# 220_cup_wash_sucction.net
KiCad netlist of a schematic drawn in EAGLE
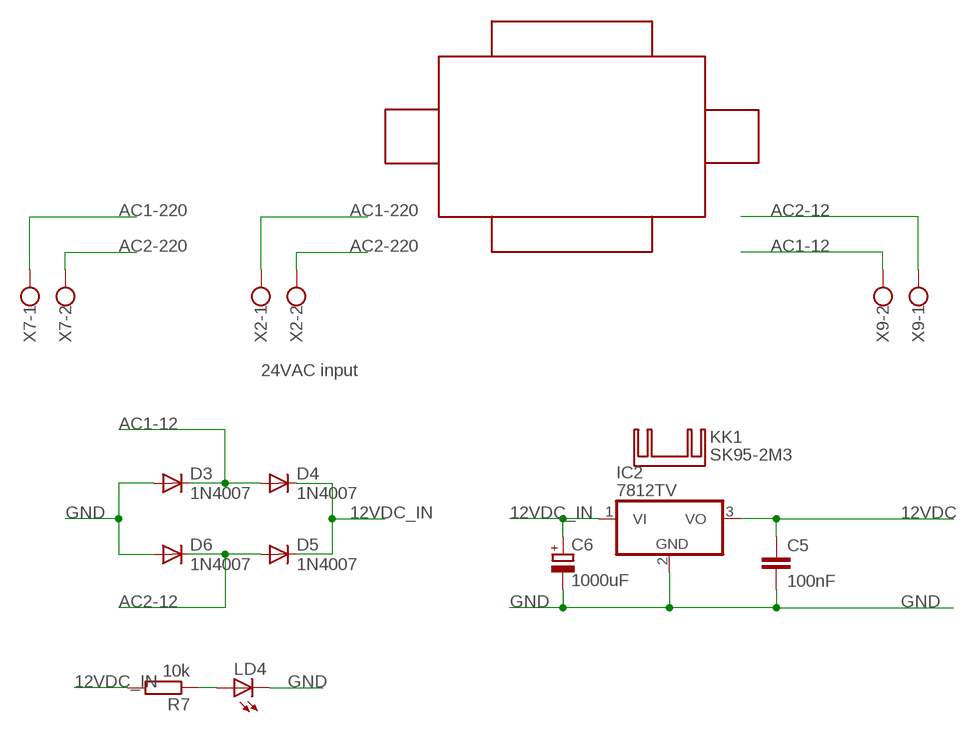
[diagram p0: schematic, sheet 1]
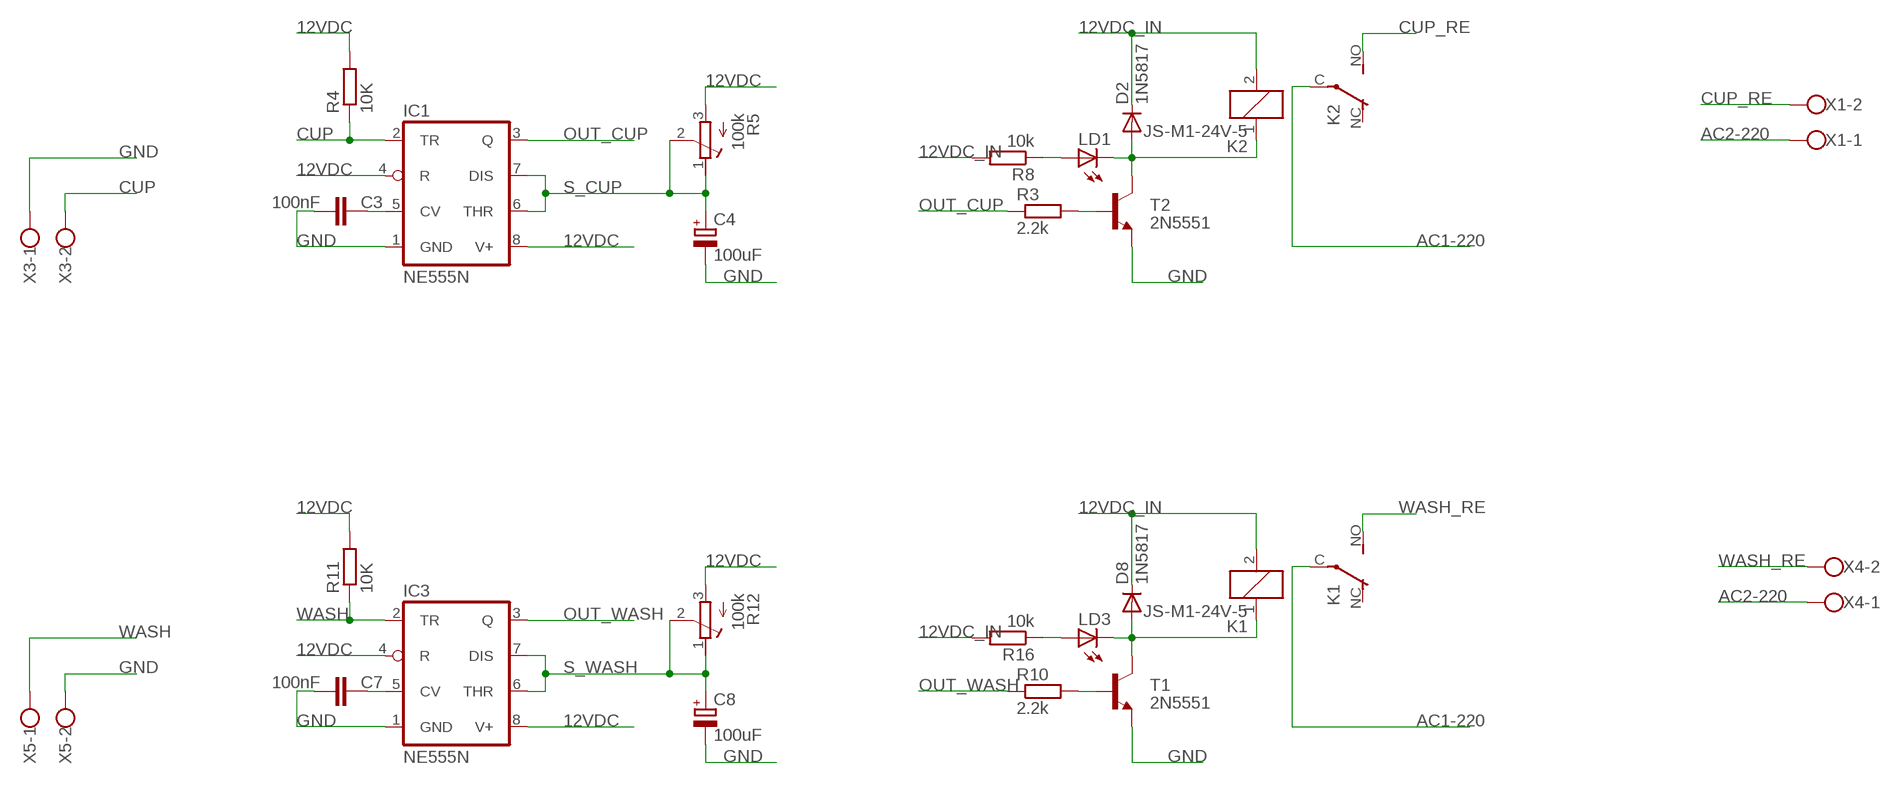
[diagram p1: schematic, sheet 2]
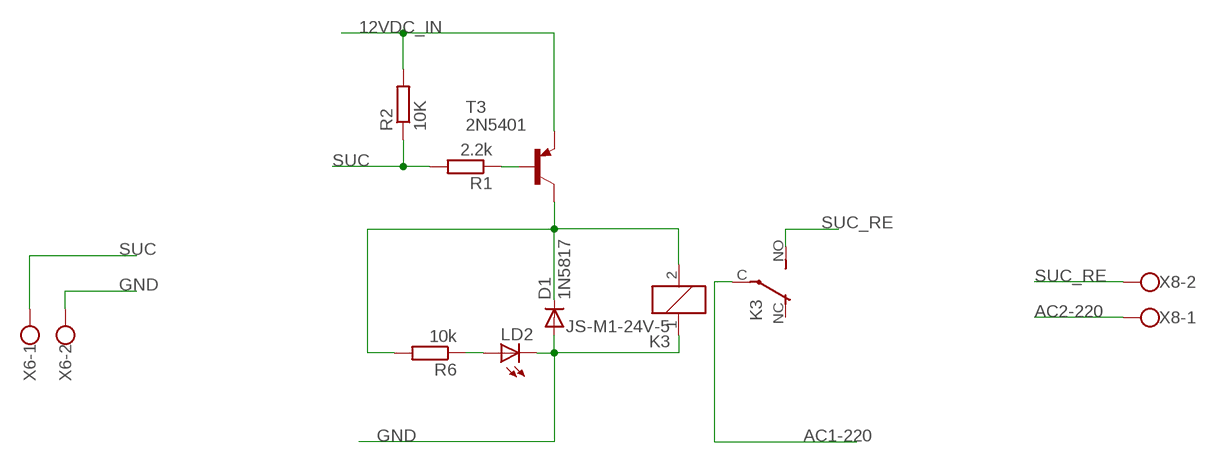
[diagram p2: schematic, sheet 3]

(export (version "E")
  (design (tool "Eeschema 10.0.6"))
  (components
    (comp (ref "D1")
      (value "1N5817")
      (footprint "eagle-import:DO41-10")
      (libsource (lib "eagle-import") (part "1N4004"))
    )
    (comp (ref "K3")
      (value "JS-M1-24V-5")
      (footprint "eagle-import:JS-M")
      (fields (field (name "MF") "FARNELL") (field (name "MPN") "JSM1-12V-5"))
      (libsource (lib "eagle-import") (part "JS-M1-12V-5"))
    )
    (comp (ref "LD2")
      (value "LED5MM")
      (footprint "eagle-import:LED5MM")
      (libsource (lib "eagle-import") (part "LED5MM"))
    )
    (comp (ref "R1")
      (value "2.2k")
      (footprint "eagle-import:0207_10")
      (libsource (lib "eagle-import") (part "R-EU_0207/10"))
    )
    (comp (ref "R2")
      (value "10K")
      (footprint "eagle-import:0207_10")
      (libsource (lib "eagle-import") (part "R-EU_0207/10"))
    )
    (comp (ref "R6")
      (value "10k")
      (footprint "eagle-import:0207_10")
      (libsource (lib "eagle-import") (part "R-EU_0207/10"))
    )
    (comp (ref "T3")
      (value "2N5401")
      (footprint "eagle-import:TO92-EBC")
      (libsource (lib "eagle-import") (part "-PNP-TO92-EBC2N5401"))
    )
    (comp (ref "X6")
      (value "W237-102")
      (footprint "eagle-import:W237-102")
      (libsource (lib "eagle-import") (part "W237-102"))
    )
    (comp (ref "X8")
      (value "W237-102")
      (footprint "eagle-import:W237-102")
      (libsource (lib "eagle-import") (part "W237-102"))
    )
    (comp (ref "C3")
      (value "100nF")
      (footprint "eagle-import:C050-025X075")
      (libsource (lib "eagle-import") (part "C-EU050-025X075"))
    )
    (comp (ref "C4")
      (value "100uF")
      (footprint "eagle-import:E3,5-8")
      (libsource (lib "eagle-import") (part "CPOL-EUE3.5-8"))
    )
    (comp (ref "C7")
      (value "100nF")
      (footprint "eagle-import:C050-025X075")
      (libsource (lib "eagle-import") (part "C-EU050-025X075"))
    )
    (comp (ref "C8")
      (value "100uF")
      (footprint "eagle-import:E3,5-8")
      (libsource (lib "eagle-import") (part "CPOL-EUE3.5-8"))
    )
    (comp (ref "D2")
      (value "1N5817")
      (footprint "eagle-import:DO41-10")
      (libsource (lib "eagle-import") (part "1N4004"))
    )
    (comp (ref "D8")
      (value "1N5817")
      (footprint "eagle-import:DO41-10")
      (libsource (lib "eagle-import") (part "1N4004"))
    )
    (comp (ref "IC1")
      (value "NE555N")
      (footprint "eagle-import:DIL08-ROUND")
      (libsource (lib "eagle-import") (part "555NNE"))
    )
    (comp (ref "IC3")
      (value "NE555N")
      (footprint "eagle-import:DIL08-ROUND")
      (libsource (lib "eagle-import") (part "555NNE"))
    )
    (comp (ref "K1")
      (value "JS-M1-24V-5")
      (footprint "eagle-import:JS-M")
      (fields (field (name "MF") "FARNELL") (field (name "MPN") "JSM1-12V-5"))
      (libsource (lib "eagle-import") (part "JS-M1-12V-5"))
    )
    (comp (ref "K2")
      (value "JS-M1-24V-5")
      (footprint "eagle-import:JS-M")
      (fields (field (name "MF") "FARNELL") (field (name "MPN") "JSM1-12V-5"))
      (libsource (lib "eagle-import") (part "JS-M1-12V-5"))
    )
    (comp (ref "LD1")
      (value "LED5MM")
      (footprint "eagle-import:LED5MM")
      (libsource (lib "eagle-import") (part "LED5MM"))
    )
    (comp (ref "LD3")
      (value "LED5MM")
      (footprint "eagle-import:LED5MM")
      (libsource (lib "eagle-import") (part "LED5MM"))
    )
    (comp (ref "R3")
      (value "2.2k")
      (footprint "eagle-import:0207_10")
      (libsource (lib "eagle-import") (part "R-EU_0207/10"))
    )
    (comp (ref "R4")
      (value "10K")
      (footprint "eagle-import:0207_10")
      (libsource (lib "eagle-import") (part "R-EU_0207/10"))
    )
    (comp (ref "R5")
      (value "100k")
      (footprint "eagle-import:RTRIMT93XA")
      (libsource (lib "eagle-import") (part "R-TRIMMT93XA"))
    )
    (comp (ref "R8")
      (value "10k")
      (footprint "eagle-import:0207_10")
      (libsource (lib "eagle-import") (part "R-EU_0207/10"))
    )
    (comp (ref "R10")
      (value "2.2k")
      (footprint "eagle-import:0207_10")
      (libsource (lib "eagle-import") (part "R-EU_0207/10"))
    )
    (comp (ref "R11")
      (value "10K")
      (footprint "eagle-import:0207_10")
      (libsource (lib "eagle-import") (part "R-EU_0207/10"))
    )
    (comp (ref "R12")
      (value "100k")
      (footprint "eagle-import:RTRIMT93XA")
      (libsource (lib "eagle-import") (part "R-TRIMMT93XA"))
    )
    (comp (ref "R16")
      (value "10k")
      (footprint "eagle-import:0207_10")
      (libsource (lib "eagle-import") (part "R-EU_0207/10"))
    )
    (comp (ref "T1")
      (value "2N5551")
      (footprint "eagle-import:TO92-EBC-OVAL")
      (libsource (lib "eagle-import") (part "2N2222"))
    )
    (comp (ref "T2")
      (value "2N5551")
      (footprint "eagle-import:TO92-EBC-OVAL")
      (libsource (lib "eagle-import") (part "2N2222"))
    )
    (comp (ref "X1")
      (value "W237-102")
      (footprint "eagle-import:W237-102")
      (libsource (lib "eagle-import") (part "W237-102"))
    )
    (comp (ref "X3")
      (value "W237-102")
      (footprint "eagle-import:W237-102")
      (libsource (lib "eagle-import") (part "W237-102"))
    )
    (comp (ref "X4")
      (value "W237-102")
      (footprint "eagle-import:W237-102")
      (libsource (lib "eagle-import") (part "W237-102"))
    )
    (comp (ref "X5")
      (value "W237-102")
      (footprint "eagle-import:W237-102")
      (libsource (lib "eagle-import") (part "W237-102"))
    )
    (comp (ref "C5")
      (value "100nF")
      (footprint "eagle-import:C050-025X075")
      (libsource (lib "eagle-import") (part "C-EU050-025X075"))
    )
    (comp (ref "C6")
      (value "1000uF")
      (footprint "eagle-import:E3,5-10")
      (libsource (lib "eagle-import") (part "CPOL-EUE3.5-10"))
    )
    (comp (ref "D3")
      (value "1N4007")
      (footprint "eagle-import:DO41-10")
      (libsource (lib "eagle-import") (part "adafruit_420_1N4004"))
    )
    (comp (ref "D4")
      (value "1N4007")
      (footprint "eagle-import:DO41-10")
      (libsource (lib "eagle-import") (part "adafruit_420_1N4004"))
    )
    (comp (ref "D5")
      (value "1N4007")
      (footprint "eagle-import:DO41-10")
      (libsource (lib "eagle-import") (part "adafruit_420_1N4004"))
    )
    (comp (ref "D6")
      (value "1N4007")
      (footprint "eagle-import:DO41-10")
      (libsource (lib "eagle-import") (part "adafruit_420_1N4004"))
    )
    (comp (ref "IC2")
      (value "7812TV")
      (footprint "eagle-import:TO220V")
      (libsource (lib "eagle-import") (part "78TV12"))
    )
    (comp (ref "KK1")
      (value "SK95-2M3")
      (footprint "eagle-import:SK95-2M3")
      (libsource (lib "eagle-import") (part "SK95-2M3"))
    )
    (comp (ref "LD4")
      (value "LED5MM")
      (footprint "eagle-import:LED5MM")
      (libsource (lib "eagle-import") (part "LED5MM"))
    )
    (comp (ref "R7")
      (value "10k")
      (footprint "eagle-import:0207_10")
      (libsource (lib "eagle-import") (part "R-EU_0207/10"))
    )
    (comp (ref "U$1")
      (value "TRANS_12V")
      (footprint "eagle-import:12V")
      (libsource (lib "eagle-import") (part "TRANS_12V"))
    )
    (comp (ref "X2")
      (value "W237-102")
      (footprint "eagle-import:W237-102")
      (libsource (lib "eagle-import") (part "W237-102"))
    )
    (comp (ref "X7")
      (value "W237-102")
      (footprint "eagle-import:W237-102")
      (libsource (lib "eagle-import") (part "W237-102"))
    )
    (comp (ref "X9")
      (value "W237-102")
      (footprint "eagle-import:W237-102")
      (libsource (lib "eagle-import") (part "W237-102"))
    )
  )
  (nets
    (net (code "1") (name "12VDC") (class "Default")
      (node (ref "C5") (pin "1") (pinfunction "1_1") (pintype "passive"))
      (node (ref "IC1") (pin "4") (pinfunction "R_4") (pintype "input"))
      (node (ref "IC1") (pin "8") (pinfunction "V+_8") (pintype "power_in"))
      (node (ref "IC2") (pin "3") (pinfunction "VO_3") (pintype "passive"))
      (node (ref "IC3") (pin "4") (pinfunction "R_4") (pintype "input"))
      (node (ref "IC3") (pin "8") (pinfunction "V+_8") (pintype "power_in"))
      (node (ref "R11") (pin "2") (pinfunction "2_2") (pintype "passive"))
      (node (ref "R12") (pin "3") (pinfunction "A_3") (pintype "passive"))
      (node (ref "R4") (pin "2") (pinfunction "2_2") (pintype "passive"))
      (node (ref "R5") (pin "3") (pinfunction "A_3") (pintype "passive"))
    )
    (net (code "2") (name "12VDC_IN") (class "Default")
      (node (ref "C6") (pin "+") (pinfunction "+_+") (pintype "passive"))
      (node (ref "D2") (pin "C") (pinfunction "C_C") (pintype "passive"))
      (node (ref "D4") (pin "C") (pinfunction "C_C") (pintype "passive"))
      (node (ref "D5") (pin "C") (pinfunction "C_C") (pintype "passive"))
      (node (ref "D8") (pin "C") (pinfunction "C_C") (pintype "passive"))
      (node (ref "IC2") (pin "1") (pinfunction "VI_1") (pintype "input"))
      (node (ref "K1") (pin "2") (pinfunction "2_2") (pintype "passive"))
      (node (ref "K2") (pin "2") (pinfunction "2_2") (pintype "passive"))
      (node (ref "R16") (pin "2") (pinfunction "2_2") (pintype "passive"))
      (node (ref "R2") (pin "2") (pinfunction "2_2") (pintype "passive"))
      (node (ref "R7") (pin "2") (pinfunction "2_2") (pintype "passive"))
      (node (ref "R8") (pin "2") (pinfunction "2_2") (pintype "passive"))
      (node (ref "T3") (pin "E") (pinfunction "E_E") (pintype "passive"))
    )
    (net (code "3") (name "AC1-12") (class "Default")
      (node (ref "D3") (pin "C") (pinfunction "C_C") (pintype "passive"))
      (node (ref "D4") (pin "A") (pinfunction "A_A") (pintype "passive"))
      (node (ref "X9") (pin "2") (pinfunction "KL_2") (pintype "passive"))
    )
    (net (code "4") (name "AC1-220") (class "Default")
      (node (ref "K1") (pin "C") (pinfunction "P_C") (pintype "passive"))
      (node (ref "K2") (pin "C") (pinfunction "P_C") (pintype "passive"))
      (node (ref "K3") (pin "C") (pinfunction "P_C") (pintype "passive"))
      (node (ref "X2") (pin "1") (pinfunction "KL_1") (pintype "passive"))
      (node (ref "X7") (pin "1") (pinfunction "KL_1") (pintype "passive"))
    )
    (net (code "5") (name "AC2-12") (class "Default")
      (node (ref "D5") (pin "A") (pinfunction "A_A") (pintype "passive"))
      (node (ref "D6") (pin "C") (pinfunction "C_C") (pintype "passive"))
      (node (ref "X9") (pin "1") (pinfunction "KL_1") (pintype "passive"))
    )
    (net (code "6") (name "AC2-220") (class "Default")
      (node (ref "X1") (pin "1") (pinfunction "KL_1") (pintype "passive"))
      (node (ref "X2") (pin "2") (pinfunction "KL_2") (pintype "passive"))
      (node (ref "X4") (pin "1") (pinfunction "KL_1") (pintype "passive"))
      (node (ref "X7") (pin "2") (pinfunction "KL_2") (pintype "passive"))
      (node (ref "X8") (pin "1") (pinfunction "KL_1") (pintype "passive"))
    )
    (net (code "7") (name "CUP") (class "Default")
      (node (ref "IC1") (pin "2") (pinfunction "TR_2") (pintype "input"))
      (node (ref "R4") (pin "1") (pinfunction "1_1") (pintype "passive"))
      (node (ref "X3") (pin "2") (pinfunction "KL_2") (pintype "passive"))
    )
    (net (code "8") (name "CUP_RE") (class "Default")
      (node (ref "K2") (pin "NO") (pinfunction "S_NO") (pintype "passive"))
      (node (ref "X1") (pin "2") (pinfunction "KL_2") (pintype "passive"))
    )
    (net (code "9") (name "GND") (class "Default")
      (node (ref "C3") (pin "2") (pinfunction "2_2") (pintype "passive"))
      (node (ref "C4") (pin "-") (pinfunction "-_-") (pintype "passive"))
      (node (ref "C5") (pin "2") (pinfunction "2_2") (pintype "passive"))
      (node (ref "C6") (pin "-") (pinfunction "-_-") (pintype "passive"))
      (node (ref "C7") (pin "2") (pinfunction "2_2") (pintype "passive"))
      (node (ref "C8") (pin "-") (pinfunction "-_-") (pintype "passive"))
      (node (ref "D1") (pin "A") (pinfunction "A_A") (pintype "passive"))
      (node (ref "D3") (pin "A") (pinfunction "A_A") (pintype "passive"))
      (node (ref "D6") (pin "A") (pinfunction "A_A") (pintype "passive"))
      (node (ref "IC1") (pin "1") (pinfunction "GND_1") (pintype "power_in"))
      (node (ref "IC2") (pin "2") (pinfunction "GND_2") (pintype "passive"))
      (node (ref "IC3") (pin "1") (pinfunction "GND_1") (pintype "power_in"))
      (node (ref "K3") (pin "1") (pinfunction "1_1") (pintype "passive"))
      (node (ref "LD2") (pin "K") (pinfunction "C_K") (pintype "passive"))
      (node (ref "LD4") (pin "K") (pinfunction "C_K") (pintype "passive"))
      (node (ref "T1") (pin "E") (pinfunction "E_E") (pintype "passive"))
      (node (ref "T2") (pin "E") (pinfunction "E_E") (pintype "passive"))
      (node (ref "X3") (pin "1") (pinfunction "KL_1") (pintype "passive"))
      (node (ref "X5") (pin "2") (pinfunction "KL_2") (pintype "passive"))
      (node (ref "X6") (pin "2") (pinfunction "KL_2") (pintype "passive"))
    )
    (net (code "10") (name "Net-(D1-PadC)") (class "Default")
      (node (ref "D1") (pin "C") (pinfunction "C_C") (pintype "passive"))
      (node (ref "K3") (pin "2") (pinfunction "2_2") (pintype "passive"))
      (node (ref "R6") (pin "2") (pinfunction "2_2") (pintype "passive"))
      (node (ref "T3") (pin "C") (pinfunction "C_C") (pintype "passive"))
    )
    (net (code "11") (name "Net-(IC1-CV)") (class "Default")
      (node (ref "C3") (pin "1") (pinfunction "1_1") (pintype "passive"))
      (node (ref "IC1") (pin "5") (pinfunction "CV_5") (pintype "input"))
    )
    (net (code "12") (name "Net-(IC3-CV)") (class "Default")
      (node (ref "C7") (pin "1") (pinfunction "1_1") (pintype "passive"))
      (node (ref "IC3") (pin "5") (pinfunction "CV_5") (pintype "input"))
    )
    (net (code "13") (name "Net-(LD1-C)") (class "Default")
      (node (ref "D2") (pin "A") (pinfunction "A_A") (pintype "passive"))
      (node (ref "K2") (pin "1") (pinfunction "1_1") (pintype "passive"))
      (node (ref "LD1") (pin "K") (pinfunction "C_K") (pintype "passive"))
      (node (ref "T2") (pin "C") (pinfunction "C_C") (pintype "passive"))
    )
    (net (code "14") (name "Net-(LD1-PadA)") (class "Default")
      (node (ref "LD1") (pin "A") (pinfunction "A_A") (pintype "passive"))
      (node (ref "R8") (pin "1") (pinfunction "1_1") (pintype "passive"))
    )
    (net (code "15") (name "Net-(LD2-PadA)") (class "Default")
      (node (ref "LD2") (pin "A") (pinfunction "A_A") (pintype "passive"))
      (node (ref "R6") (pin "1") (pinfunction "1_1") (pintype "passive"))
    )
    (net (code "16") (name "Net-(LD3-C)") (class "Default")
      (node (ref "D8") (pin "A") (pinfunction "A_A") (pintype "passive"))
      (node (ref "K1") (pin "1") (pinfunction "1_1") (pintype "passive"))
      (node (ref "LD3") (pin "K") (pinfunction "C_K") (pintype "passive"))
      (node (ref "T1") (pin "C") (pinfunction "C_C") (pintype "passive"))
    )
    (net (code "17") (name "Net-(LD3-PadA)") (class "Default")
      (node (ref "LD3") (pin "A") (pinfunction "A_A") (pintype "passive"))
      (node (ref "R16") (pin "1") (pinfunction "1_1") (pintype "passive"))
    )
    (net (code "18") (name "Net-(LD4-PadA)") (class "Default")
      (node (ref "LD4") (pin "A") (pinfunction "A_A") (pintype "passive"))
      (node (ref "R7") (pin "1") (pinfunction "1_1") (pintype "passive"))
    )
    (net (code "19") (name "Net-(R1-Pad1)") (class "Default")
      (node (ref "R1") (pin "1") (pinfunction "1_1") (pintype "passive"))
      (node (ref "T3") (pin "B") (pinfunction "B_B") (pintype "passive"))
    )
    (net (code "20") (name "Net-(R3-Pad2)") (class "Default")
      (node (ref "R3") (pin "2") (pinfunction "2_2") (pintype "passive"))
      (node (ref "T2") (pin "B") (pinfunction "B_B") (pintype "passive"))
    )
    (net (code "21") (name "Net-(R10-Pad2)") (class "Default")
      (node (ref "R10") (pin "2") (pinfunction "2_2") (pintype "passive"))
      (node (ref "T1") (pin "B") (pinfunction "B_B") (pintype "passive"))
    )
    (net (code "22") (name "OUT_CUP") (class "Default")
      (node (ref "IC1") (pin "3") (pinfunction "Q_3") (pintype "output"))
      (node (ref "R3") (pin "1") (pinfunction "1_1") (pintype "passive"))
    )
    (net (code "23") (name "OUT_WASH") (class "Default")
      (node (ref "IC3") (pin "3") (pinfunction "Q_3") (pintype "output"))
      (node (ref "R10") (pin "1") (pinfunction "1_1") (pintype "passive"))
    )
    (net (code "24") (name "SUC") (class "Default")
      (node (ref "R1") (pin "2") (pinfunction "2_2") (pintype "passive"))
      (node (ref "R2") (pin "1") (pinfunction "1_1") (pintype "passive"))
      (node (ref "X6") (pin "1") (pinfunction "KL_1") (pintype "passive"))
    )
    (net (code "25") (name "SUC_RE") (class "Default")
      (node (ref "K3") (pin "NO") (pinfunction "S_NO") (pintype "passive"))
      (node (ref "X8") (pin "2") (pinfunction "KL_2") (pintype "passive"))
    )
    (net (code "26") (name "S_CUP") (class "Default")
      (node (ref "C4") (pin "+") (pinfunction "+_+") (pintype "passive"))
      (node (ref "IC1") (pin "6") (pinfunction "THR_6") (pintype "input"))
      (node (ref "IC1") (pin "7") (pinfunction "DIS_7") (pintype "input"))
      (node (ref "R5") (pin "1") (pinfunction "E_1") (pintype "passive"))
      (node (ref "R5") (pin "2") (pinfunction "S_2") (pintype "passive"))
    )
    (net (code "27") (name "S_WASH") (class "Default")
      (node (ref "C8") (pin "+") (pinfunction "+_+") (pintype "passive"))
      (node (ref "IC3") (pin "6") (pinfunction "THR_6") (pintype "input"))
      (node (ref "IC3") (pin "7") (pinfunction "DIS_7") (pintype "input"))
      (node (ref "R12") (pin "1") (pinfunction "E_1") (pintype "passive"))
      (node (ref "R12") (pin "2") (pinfunction "S_2") (pintype "passive"))
    )
    (net (code "28") (name "WASH") (class "Default")
      (node (ref "IC3") (pin "2") (pinfunction "TR_2") (pintype "input"))
      (node (ref "R11") (pin "1") (pinfunction "1_1") (pintype "passive"))
      (node (ref "X5") (pin "1") (pinfunction "KL_1") (pintype "passive"))
    )
    (net (code "29") (name "WASH_RE") (class "Default")
      (node (ref "K1") (pin "NO") (pinfunction "S_NO") (pintype "passive"))
      (node (ref "X4") (pin "2") (pinfunction "KL_2") (pintype "passive"))
    )
    (net (code "30") (name "unconnected-(K1B-O-PadNC)") (class "Default")
      (node (ref "K1") (pin "NC") (pinfunction "O_NC") (pintype "passive"))
    )
    (net (code "31") (name "unconnected-(K2B-O-PadNC)") (class "Default")
      (node (ref "K2") (pin "NC") (pinfunction "O_NC") (pintype "passive"))
    )
    (net (code "32") (name "unconnected-(K3B-O-PadNC)") (class "Default")
      (node (ref "K3") (pin "NC") (pinfunction "O_NC") (pintype "passive"))
    )
  )
)
